# ASBB_USBUART.net
KiCad netlist of a schematic drawn in Altium Designer
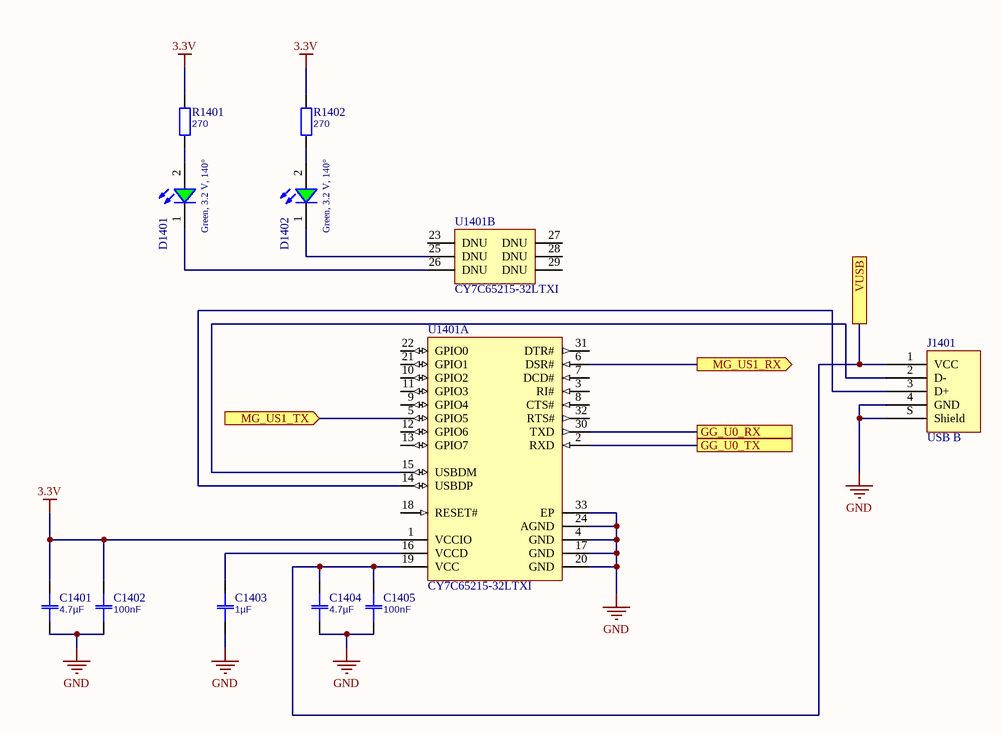
[diagram p0: ASBB_USBUART.SchDoc]

(export (version "E")
  (design (tool "Eeschema 10.0.6"))
  (components
    (comp (ref "C1401")
      (value "4.7µF")
      (footprint "0603")
      (description "Capacitor")
      (fields (field (name "PARTNUMBER") "?"))
      (libsource (lib "FZI") (part "Capacitor"))
    )
    (comp (ref "C1402")
      (value "100nF")
      (footprint "0603")
      (description "Capacitor")
      (fields (field (name "PARTNUMBER") "?"))
      (libsource (lib "FZI") (part "Capacitor"))
    )
    (comp (ref "C1403")
      (value "1µF")
      (footprint "0603")
      (description "Capacitor")
      (fields (field (name "PARTNUMBER") "?"))
      (libsource (lib "FZI") (part "Capacitor"))
    )
    (comp (ref "C1404")
      (value "4.7µF")
      (footprint "0603")
      (description "Capacitor")
      (fields (field (name "PARTNUMBER") "?"))
      (libsource (lib "FZI") (part "Capacitor"))
    )
    (comp (ref "C1405")
      (value "100nF")
      (footprint "0603")
      (description "Capacitor")
      (fields (field (name "PARTNUMBER") "?"))
      (libsource (lib "FZI") (part "Capacitor"))
    )
    (comp (ref "D1401")
      (value "Green, 3.2 V, 140°")
      (footprint "WL-SMCW_0603")
      (description "WL-SMCW SMD Mono-color Chip LED Waterclear, size 0603, Green, 3.2 V, 140°")
      (fields (field (name "PART NUMBER") "150060GS75000") (field (name "PUBLISHER") "Wurth Elektronik"))
      (libsource (lib "ALTIUM-WL-SMCW-rev18b") (part "150060GS75000"))
    )
    (comp (ref "D1402")
      (value "Green, 3.2 V, 140°")
      (footprint "WL-SMCW_0603")
      (description "WL-SMCW SMD Mono-color Chip LED Waterclear, size 0603, Green, 3.2 V, 140°")
      (fields (field (name "PART NUMBER") "150060GS75000") (field (name "PUBLISHER") "Wurth Elektronik"))
      (libsource (lib "ALTIUM-WL-SMCW-rev18b") (part "150060GS75000"))
    )
    (comp (ref "J1401")
      (value "USB B")
      (footprint "FCI USB 10118193-0001LF")
      (libsource (lib "Connectors") (part "USB 2.0 Type B"))
    )
    (comp (ref "R1401")
      (value "270")
      (footprint "0603")
      (description "Resistor")
      (fields (field (name "PARTNUMBER") "?"))
      (libsource (lib "FZI") (part "Resistor"))
    )
    (comp (ref "R1402")
      (value "270")
      (footprint "0603")
      (description "Resistor")
      (fields (field (name "PARTNUMBER") "?"))
      (libsource (lib "FZI") (part "Resistor"))
    )
    (comp (ref "U1401")
      (value "CY7C65215-32LTXI")
      (footprint "CYP-LTX32_N")
      (fields (field (name "MANUFACTURER") "Cypress"))
      (libsource (lib "Cypress USB Controllers") (part "CY7C65215-32LTXI"))
    )
  )
  (nets
    (net (code "1") (name "/GG_U0_RX") (class "Default")
      (node (ref "U1401") (pin "30") (pinfunction "TXD_30") (pintype "output"))
    )
    (net (code "2") (name "/GG_U0_TX") (class "Default")
      (node (ref "U1401") (pin "2") (pinfunction "RXD_2") (pintype "input"))
    )
    (net (code "3") (name "/MG_US1_RX") (class "Default")
      (node (ref "U1401") (pin "6") (pinfunction "DSR#_6") (pintype "input"))
    )
    (net (code "4") (name "/MG_US1_TX") (class "Default")
      (node (ref "U1401") (pin "5") (pinfunction "GPIO5_5") (pintype "bidirectional"))
    )
    (net (code "5") (name "/VUSB") (class "Default")
      (node (ref "C1404") (pin "2") (pinfunction "2_2") (pintype "passive"))
      (node (ref "C1405") (pin "2") (pinfunction "2_2") (pintype "passive"))
      (node (ref "J1401") (pin "1") (pinfunction "VCC_1") (pintype "passive"))
      (node (ref "U1401") (pin "19") (pinfunction "VCC_19") (pintype "power_in"))
    )
    (net (code "6") (name "3.3V") (class "Default")
      (node (ref "C1401") (pin "2") (pinfunction "2_2") (pintype "passive"))
      (node (ref "C1402") (pin "2") (pinfunction "2_2") (pintype "passive"))
      (node (ref "R1401") (pin "2") (pinfunction "2_2") (pintype "passive"))
      (node (ref "R1402") (pin "2") (pinfunction "2_2") (pintype "passive"))
      (node (ref "U1401") (pin "1") (pinfunction "VCCIO_1") (pintype "power_in"))
    )
    (net (code "7") (name "GND") (class "Default")
      (node (ref "C1401") (pin "1") (pinfunction "1_1") (pintype "passive"))
      (node (ref "C1402") (pin "1") (pinfunction "1_1") (pintype "passive"))
      (node (ref "C1403") (pin "1") (pinfunction "1_1") (pintype "passive"))
      (node (ref "C1404") (pin "1") (pinfunction "1_1") (pintype "passive"))
      (node (ref "C1405") (pin "1") (pinfunction "1_1") (pintype "passive"))
      (node (ref "J1401") (pin "4") (pinfunction "GND_4") (pintype "passive"))
      (node (ref "J1401") (pin "S") (pinfunction "Shield_S") (pintype "passive"))
      (node (ref "U1401") (pin "17") (pinfunction "GND_17") (pintype "power_in"))
      (node (ref "U1401") (pin "20") (pinfunction "GND_20") (pintype "power_in"))
      (node (ref "U1401") (pin "24") (pinfunction "AGND_24") (pintype "power_in"))
      (node (ref "U1401") (pin "33") (pinfunction "EP_33") (pintype "passive"))
      (node (ref "U1401") (pin "4") (pinfunction "GND_4") (pintype "power_in"))
    )
    (net (code "8") (name "Net-(D1401-A)") (class "Default")
      (node (ref "D1401") (pin "2") (pinfunction "A_2") (pintype "passive"))
      (node (ref "R1401") (pin "1") (pinfunction "1_1") (pintype "passive"))
    )
    (net (code "9") (name "Net-(D1401-K)") (class "Default")
      (node (ref "D1401") (pin "1") (pinfunction "K_1") (pintype "passive"))
      (node (ref "U1401") (pin "26") (pinfunction "DNU_26") (pintype "passive"))
    )
    (net (code "10") (name "Net-(D1402-A)") (class "Default")
      (node (ref "D1402") (pin "2") (pinfunction "A_2") (pintype "passive"))
      (node (ref "R1402") (pin "1") (pinfunction "1_1") (pintype "passive"))
    )
    (net (code "11") (name "Net-(D1402-K)") (class "Default")
      (node (ref "D1402") (pin "1") (pinfunction "K_1") (pintype "passive"))
      (node (ref "U1401") (pin "25") (pinfunction "DNU_25") (pintype "passive"))
    )
    (net (code "12") (name "Net-(J1401-D+)") (class "Default")
      (node (ref "J1401") (pin "3") (pinfunction "D+_3") (pintype "passive"))
      (node (ref "U1401") (pin "14") (pinfunction "USBDP_14") (pintype "bidirectional"))
    )
    (net (code "13") (name "Net-(J1401-D-)") (class "Default")
      (node (ref "J1401") (pin "2") (pinfunction "D-_2") (pintype "passive"))
      (node (ref "U1401") (pin "15") (pinfunction "USBDM_15") (pintype "bidirectional"))
    )
    (net (code "14") (name "Net-(U1401A-VCCD)") (class "Default")
      (node (ref "C1403") (pin "2") (pinfunction "2_2") (pintype "passive"))
      (node (ref "U1401") (pin "16") (pinfunction "VCCD_16") (pintype "power_in"))
    )
    (net (code "15") (name "unconnected-(U1401A-CTS#-Pad8)") (class "Default")
      (node (ref "U1401") (pin "8") (pinfunction "CTS#_8") (pintype "input"))
    )
    (net (code "16") (name "unconnected-(U1401A-DCD#-Pad7)") (class "Default")
      (node (ref "U1401") (pin "7") (pinfunction "DCD#_7") (pintype "input"))
    )
    (net (code "17") (name "unconnected-(U1401A-DTR#-Pad31)") (class "Default")
      (node (ref "U1401") (pin "31") (pinfunction "DTR#_31") (pintype "output"))
    )
    (net (code "18") (name "unconnected-(U1401A-GPIO0-Pad22)") (class "Default")
      (node (ref "U1401") (pin "22") (pinfunction "GPIO0_22") (pintype "bidirectional"))
    )
    (net (code "19") (name "unconnected-(U1401A-GPIO1-Pad21)") (class "Default")
      (node (ref "U1401") (pin "21") (pinfunction "GPIO1_21") (pintype "bidirectional"))
    )
    (net (code "20") (name "unconnected-(U1401A-GPIO2-Pad10)") (class "Default")
      (node (ref "U1401") (pin "10") (pinfunction "GPIO2_10") (pintype "bidirectional"))
    )
    (net (code "21") (name "unconnected-(U1401A-GPIO3-Pad11)") (class "Default")
      (node (ref "U1401") (pin "11") (pinfunction "GPIO3_11") (pintype "bidirectional"))
    )
    (net (code "22") (name "unconnected-(U1401A-GPIO4-Pad9)") (class "Default")
      (node (ref "U1401") (pin "9") (pinfunction "GPIO4_9") (pintype "bidirectional"))
    )
    (net (code "23") (name "unconnected-(U1401A-GPIO6-Pad12)") (class "Default")
      (node (ref "U1401") (pin "12") (pinfunction "GPIO6_12") (pintype "bidirectional"))
    )
    (net (code "24") (name "unconnected-(U1401A-GPIO7-Pad13)") (class "Default")
      (node (ref "U1401") (pin "13") (pinfunction "GPIO7_13") (pintype "bidirectional"))
    )
    (net (code "25") (name "unconnected-(U1401A-RESET#-Pad18)") (class "Default")
      (node (ref "U1401") (pin "18") (pinfunction "RESET#_18") (pintype "input"))
    )
    (net (code "26") (name "unconnected-(U1401A-RI#-Pad3)") (class "Default")
      (node (ref "U1401") (pin "3") (pinfunction "RI#_3") (pintype "input"))
    )
    (net (code "27") (name "unconnected-(U1401A-RTS#-Pad32)") (class "Default")
      (node (ref "U1401") (pin "32") (pinfunction "RTS#_32") (pintype "output"))
    )
    (net (code "28") (name "unconnected-(U1401B-DNU-Pad23)") (class "Default")
      (node (ref "U1401") (pin "23") (pinfunction "DNU_23") (pintype "passive"))
    )
    (net (code "29") (name "unconnected-(U1401B-DNU-Pad27)") (class "Default")
      (node (ref "U1401") (pin "27") (pinfunction "DNU_27") (pintype "passive"))
    )
    (net (code "30") (name "unconnected-(U1401B-DNU-Pad28)") (class "Default")
      (node (ref "U1401") (pin "28") (pinfunction "DNU_28") (pintype "passive"))
    )
    (net (code "31") (name "unconnected-(U1401B-DNU-Pad29)") (class "Default")
      (node (ref "U1401") (pin "29") (pinfunction "DNU_29") (pintype "passive"))
    )
  )
)
